# Grove-LED_Socket_Kit_v1_0b.net
KiCad netlist of a schematic drawn in EAGLE
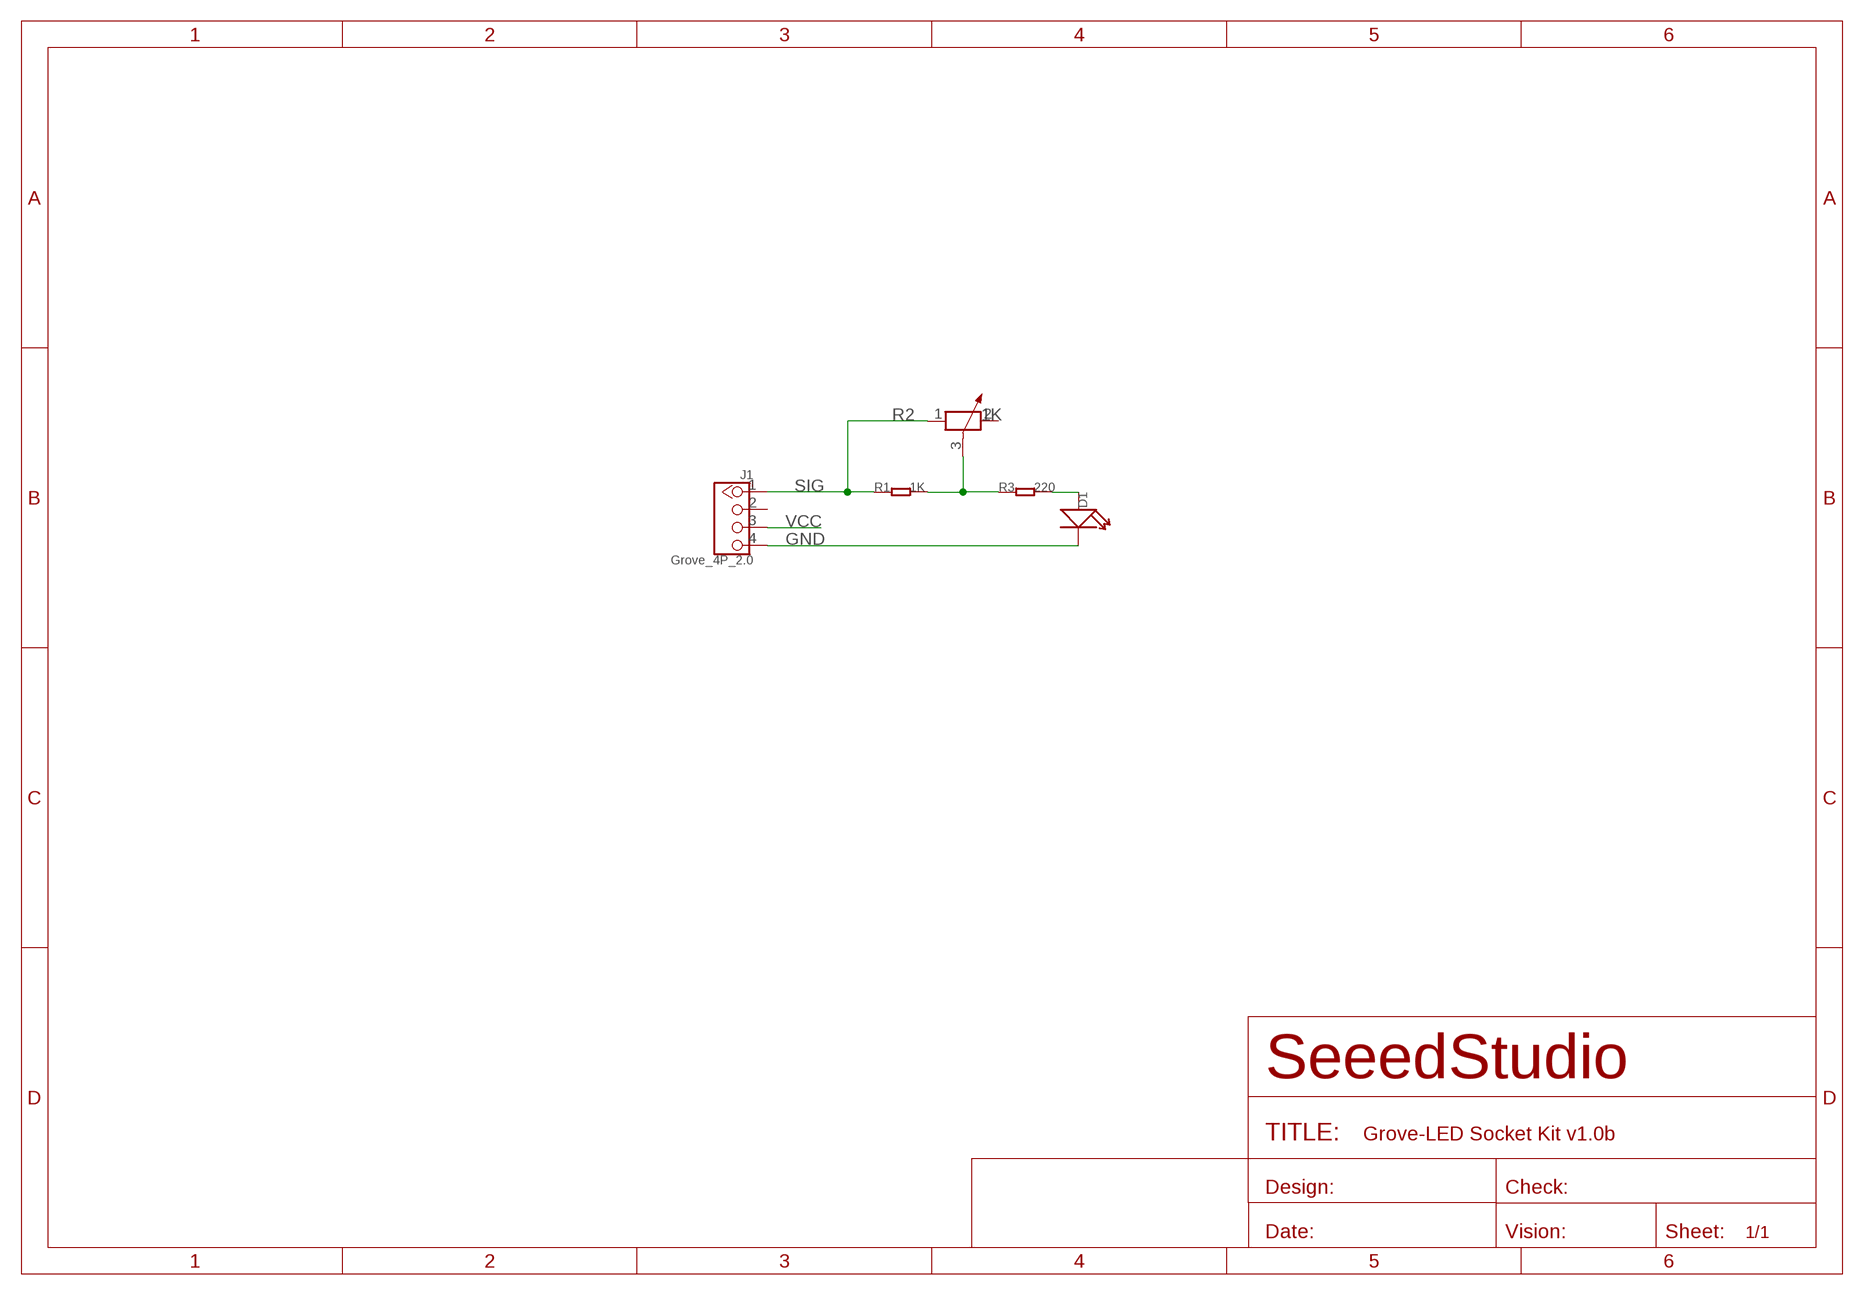
[diagram p0: schematic, sheet 1]

(export (version "E")
  (design (tool "Eeschema 10.0.6"))
  (components
    (comp (ref "D1")
      (value "LED-6MM")
      (footprint "eagle-import:LED-2P-2.54-6MM")
      (libsource (lib "eagle-import") (part "LED-6MM"))
    )
    (comp (ref "J1")
      (value "Grove_4P_2.0")
      (footprint "eagle-import:2.0_1X4")
      (libsource (lib "eagle-import") (part "TWIG_2.0"))
    )
    (comp (ref "R1")
      (value "1K")
      (footprint "eagle-import:0603")
      (libsource (lib "eagle-import") (part "005-R0603"))
    )
    (comp (ref "R2")
      (value "1K")
      (footprint "eagle-import:3P-SQUA-7X6.8")
      (libsource (lib "eagle-import") (part "R-POTENTIOMETER'3362'"))
    )
    (comp (ref "R3")
      (value "220")
      (footprint "eagle-import:0603")
      (libsource (lib "eagle-import") (part "005-R0603"))
    )
  )
  (nets
    (net (code "1") (name "/GND") (class "Default")
      (node (ref "D1") (pin "-") (pinfunction "-_-") (pintype "passive"))
      (node (ref "J1") (pin "4") (pinfunction "4_4") (pintype "bidirectional"))
    )
    (net (code "2") (name "/SIG") (class "Default")
      (node (ref "J1") (pin "1") (pinfunction "1_1") (pintype "bidirectional"))
      (node (ref "R1") (pin "1") (pinfunction "1_1") (pintype "passive"))
      (node (ref "R2") (pin "1") (pinfunction "1_1") (pintype "passive"))
    )
    (net (code "3") (name "/VCC") (class "Default")
      (node (ref "J1") (pin "3") (pinfunction "3_3") (pintype "bidirectional"))
    )
    (net (code "4") (name "Net-(D1-Pad+)") (class "Default")
      (node (ref "D1") (pin "+") (pinfunction "+_+") (pintype "passive"))
      (node (ref "R3") (pin "2") (pinfunction "2_2") (pintype "passive"))
    )
    (net (code "5") (name "Net-(R1-Pad2)") (class "Default")
      (node (ref "R1") (pin "2") (pinfunction "2_2") (pintype "passive"))
      (node (ref "R2") (pin "3") (pinfunction "3_3") (pintype "passive"))
      (node (ref "R3") (pin "1") (pinfunction "1_1") (pintype "passive"))
    )
    (net (code "6") (name "unconnected-(J1-Pad2)") (class "Default")
      (node (ref "J1") (pin "2") (pinfunction "2_2") (pintype "bidirectional"))
    )
    (net (code "7") (name "unconnected-(R2-Pad2)") (class "Default")
      (node (ref "R2") (pin "2") (pinfunction "2_2") (pintype "passive"))
    )
  )
)
